# schematic_slave_3_LVDT.net
KiCad netlist of a schematic drawn in EAGLE
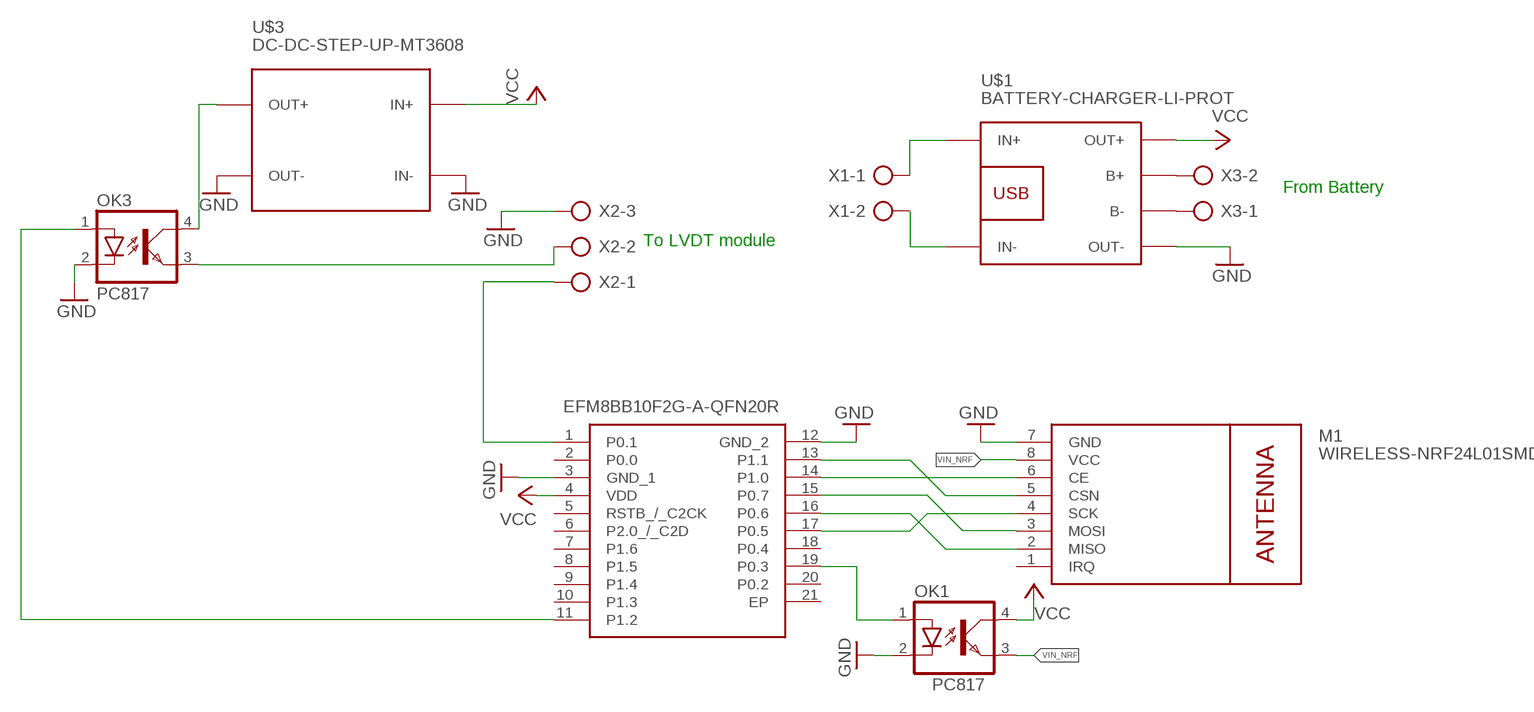
[diagram p0: schematic, sheet 1]

(export (version "E")
  (design (tool "Eeschema 10.0.6"))
  (components
    (comp (ref "IC1")
      (value "EFM8BB10F2G-A-QFN20R")
      (footprint "eagle-import:EFM8BB10F2GAQFN20R")
      (fields (field (name "MOUSER_PART_NUMBER") "634-8BB10F2GAQF20R"))
      (libsource (lib "eagle-import") (part "EFM8BB10F2G-A-QFN20R"))
    )
    (comp (ref "M1")
      (value "WIRELESS-NRF24L01SMD")
      (footprint "eagle-import:WIRELESS-NRF24L01-SMD")
      (libsource (lib "eagle-import") (part "WIRELESS-NRF24L01SMD"))
    )
    (comp (ref "OK1")
      (value "PC817")
      (footprint "eagle-import:DIL04")
      (fields (field (name "MPN") "PC817X4J000F"))
      (libsource (lib "eagle-import") (part "PC817"))
    )
    (comp (ref "OK3")
      (value "PC817")
      (footprint "eagle-import:DIL04")
      (fields (field (name "MPN") "PC817X4J000F"))
      (libsource (lib "eagle-import") (part "PC817"))
    )
    (comp (ref "U$1")
      (value "BATTERY-CHARGER-LI-PROT")
      (footprint "eagle-import:BATTERY-CHARGER-LI-PROT")
      (libsource (lib "eagle-import") (part "BATTERY-CHARGER-LI-PROT"))
    )
    (comp (ref "U$3")
      (value "DC-DC-STEP-UP-MT3608")
      (footprint "eagle-import:DC-DC-STEP-UP-MT3608")
      (libsource (lib "eagle-import") (part "DC-DC-STEP-UP-MT3608"))
    )
    (comp (ref "X1")
      (value "AK500/2-H")
      (footprint "eagle-import:AK500_2-H")
      (libsource (lib "eagle-import") (part "AK500/2-H"))
    )
    (comp (ref "X2")
      (value "AK500/3-H")
      (footprint "eagle-import:AK500_3-H")
      (libsource (lib "eagle-import") (part "AK500/3-H"))
    )
    (comp (ref "X3")
      (value "AK500/2-H")
      (footprint "eagle-import:AK500_2-H")
      (libsource (lib "eagle-import") (part "AK500/2-H"))
    )
  )
  (nets
    (net (code "1") (name "GND") (class "Default")
      (node (ref "IC1") (pin "12") (pinfunction "GND_2_12") (pintype "bidirectional"))
      (node (ref "IC1") (pin "3") (pinfunction "GND_1_3") (pintype "bidirectional"))
      (node (ref "M1") (pin "7") (pinfunction "GND_7") (pintype "power_in"))
      (node (ref "OK1") (pin "2") (pinfunction "C_2") (pintype "passive"))
      (node (ref "OK3") (pin "2") (pinfunction "C_2") (pintype "passive"))
      (node (ref "U$1") (pin "OUT-") (pinfunction "OUT-_OUT-") (pintype "bidirectional"))
      (node (ref "U$3") (pin "IN-") (pinfunction "IN-_IN-") (pintype "bidirectional"))
      (node (ref "U$3") (pin "OUT-") (pinfunction "OUT-_OUT-") (pintype "bidirectional"))
      (node (ref "X2") (pin "3") (pinfunction "KL_3") (pintype "passive"))
    )
    (net (code "2") (name "Net-(IC1-P0.1)") (class "Default")
      (node (ref "IC1") (pin "1") (pinfunction "P0.1_1") (pintype "bidirectional"))
      (node (ref "X2") (pin "1") (pinfunction "KL_1") (pintype "passive"))
    )
    (net (code "3") (name "Net-(IC1-P0.3)") (class "Default")
      (node (ref "IC1") (pin "19") (pinfunction "P0.3_19") (pintype "bidirectional"))
      (node (ref "OK1") (pin "1") (pinfunction "A_1") (pintype "passive"))
    )
    (net (code "4") (name "Net-(IC1-P0.5)") (class "Default")
      (node (ref "IC1") (pin "17") (pinfunction "P0.5_17") (pintype "bidirectional"))
      (node (ref "M1") (pin "4") (pinfunction "SCK_4") (pintype "bidirectional"))
    )
    (net (code "5") (name "Net-(IC1-P0.6)") (class "Default")
      (node (ref "IC1") (pin "16") (pinfunction "P0.6_16") (pintype "bidirectional"))
      (node (ref "M1") (pin "2") (pinfunction "MISO_2") (pintype "bidirectional"))
    )
    (net (code "6") (name "Net-(IC1-P0.7)") (class "Default")
      (node (ref "IC1") (pin "15") (pinfunction "P0.7_15") (pintype "bidirectional"))
      (node (ref "M1") (pin "3") (pinfunction "MOSI_3") (pintype "bidirectional"))
    )
    (net (code "7") (name "Net-(IC1-P1.0)") (class "Default")
      (node (ref "IC1") (pin "14") (pinfunction "P1.0_14") (pintype "bidirectional"))
      (node (ref "M1") (pin "6") (pinfunction "CE_6") (pintype "bidirectional"))
    )
    (net (code "8") (name "Net-(IC1-P1.1)") (class "Default")
      (node (ref "IC1") (pin "13") (pinfunction "P1.1_13") (pintype "bidirectional"))
      (node (ref "M1") (pin "5") (pinfunction "CSN_5") (pintype "bidirectional"))
    )
    (net (code "9") (name "Net-(IC1-P1.2)") (class "Default")
      (node (ref "IC1") (pin "11") (pinfunction "P1.2_11") (pintype "bidirectional"))
      (node (ref "OK3") (pin "1") (pinfunction "A_1") (pintype "passive"))
    )
    (net (code "10") (name "Net-(OK3-COL)") (class "Default")
      (node (ref "OK3") (pin "4") (pinfunction "COL_4") (pintype "passive"))
      (node (ref "U$3") (pin "OUT+") (pinfunction "OUT+_OUT+") (pintype "bidirectional"))
    )
    (net (code "11") (name "Net-(OK3-EMIT)") (class "Default")
      (node (ref "OK3") (pin "3") (pinfunction "EMIT_3") (pintype "passive"))
      (node (ref "X2") (pin "2") (pinfunction "KL_2") (pintype "passive"))
    )
    (net (code "12") (name "Net-(X1A-KL)") (class "Default")
      (node (ref "U$1") (pin "IN+") (pinfunction "IN+_IN+") (pintype "bidirectional"))
      (node (ref "X1") (pin "1") (pinfunction "KL_1") (pintype "passive"))
    )
    (net (code "13") (name "Net-(X1B-KL)") (class "Default")
      (node (ref "U$1") (pin "IN-") (pinfunction "IN-_IN-") (pintype "bidirectional"))
      (node (ref "X1") (pin "2") (pinfunction "KL_2") (pintype "passive"))
    )
    (net (code "14") (name "Net-(X3A-KL)") (class "Default")
      (node (ref "U$1") (pin "B-") (pinfunction "B-_B-") (pintype "bidirectional"))
      (node (ref "X3") (pin "1") (pinfunction "KL_1") (pintype "passive"))
    )
    (net (code "15") (name "Net-(X3B-KL)") (class "Default")
      (node (ref "U$1") (pin "B+") (pinfunction "B+_B+") (pintype "bidirectional"))
      (node (ref "X3") (pin "2") (pinfunction "KL_2") (pintype "passive"))
    )
    (net (code "16") (name "VCC") (class "Default")
      (node (ref "IC1") (pin "4") (pinfunction "VDD_4") (pintype "bidirectional"))
      (node (ref "OK1") (pin "4") (pinfunction "COL_4") (pintype "passive"))
      (node (ref "U$1") (pin "OUT+") (pinfunction "OUT+_OUT+") (pintype "bidirectional"))
      (node (ref "U$3") (pin "IN+") (pinfunction "IN+_IN+") (pintype "bidirectional"))
    )
    (net (code "17") (name "VIN_NRF") (class "Default")
      (node (ref "M1") (pin "8") (pinfunction "VCC_8") (pintype "power_in"))
      (node (ref "OK1") (pin "3") (pinfunction "EMIT_3") (pintype "passive"))
    )
    (net (code "18") (name "unconnected-(IC1-EP-Pad21)") (class "Default")
      (node (ref "IC1") (pin "21") (pinfunction "EP_21") (pintype "bidirectional"))
    )
    (net (code "19") (name "unconnected-(IC1-P0.0-Pad2)") (class "Default")
      (node (ref "IC1") (pin "2") (pinfunction "P0.0_2") (pintype "bidirectional"))
    )
    (net (code "20") (name "unconnected-(IC1-P0.2-Pad20)") (class "Default")
      (node (ref "IC1") (pin "20") (pinfunction "P0.2_20") (pintype "bidirectional"))
    )
    (net (code "21") (name "unconnected-(IC1-P0.4-Pad18)") (class "Default")
      (node (ref "IC1") (pin "18") (pinfunction "P0.4_18") (pintype "bidirectional"))
    )
    (net (code "22") (name "unconnected-(IC1-P1.3-Pad10)") (class "Default")
      (node (ref "IC1") (pin "10") (pinfunction "P1.3_10") (pintype "bidirectional"))
    )
    (net (code "23") (name "unconnected-(IC1-P1.4-Pad9)") (class "Default")
      (node (ref "IC1") (pin "9") (pinfunction "P1.4_9") (pintype "bidirectional"))
    )
    (net (code "24") (name "unconnected-(IC1-P1.5-Pad8)") (class "Default")
      (node (ref "IC1") (pin "8") (pinfunction "P1.5_8") (pintype "bidirectional"))
    )
    (net (code "25") (name "unconnected-(IC1-P1.6-Pad7)") (class "Default")
      (node (ref "IC1") (pin "7") (pinfunction "P1.6_7") (pintype "bidirectional"))
    )
    (net (code "26") (name "unconnected-(IC1-P2.0_{slash}_C2D-Pad6)") (class "Default")
      (node (ref "IC1") (pin "6") (pinfunction "P2.0_/_C2D_6") (pintype "bidirectional"))
    )
    (net (code "27") (name "unconnected-(IC1-RSTB_{slash}_C2CK-Pad5)") (class "Default")
      (node (ref "IC1") (pin "5") (pinfunction "RSTB_/_C2CK_5") (pintype "bidirectional"))
    )
    (net (code "28") (name "unconnected-(M1-IRQ-Pad1)") (class "Default")
      (node (ref "M1") (pin "1") (pinfunction "IRQ_1") (pintype "bidirectional"))
    )
  )
)
